# CH32V103C-R0.net
KiCad netlist of a schematic drawn in Altium Designer
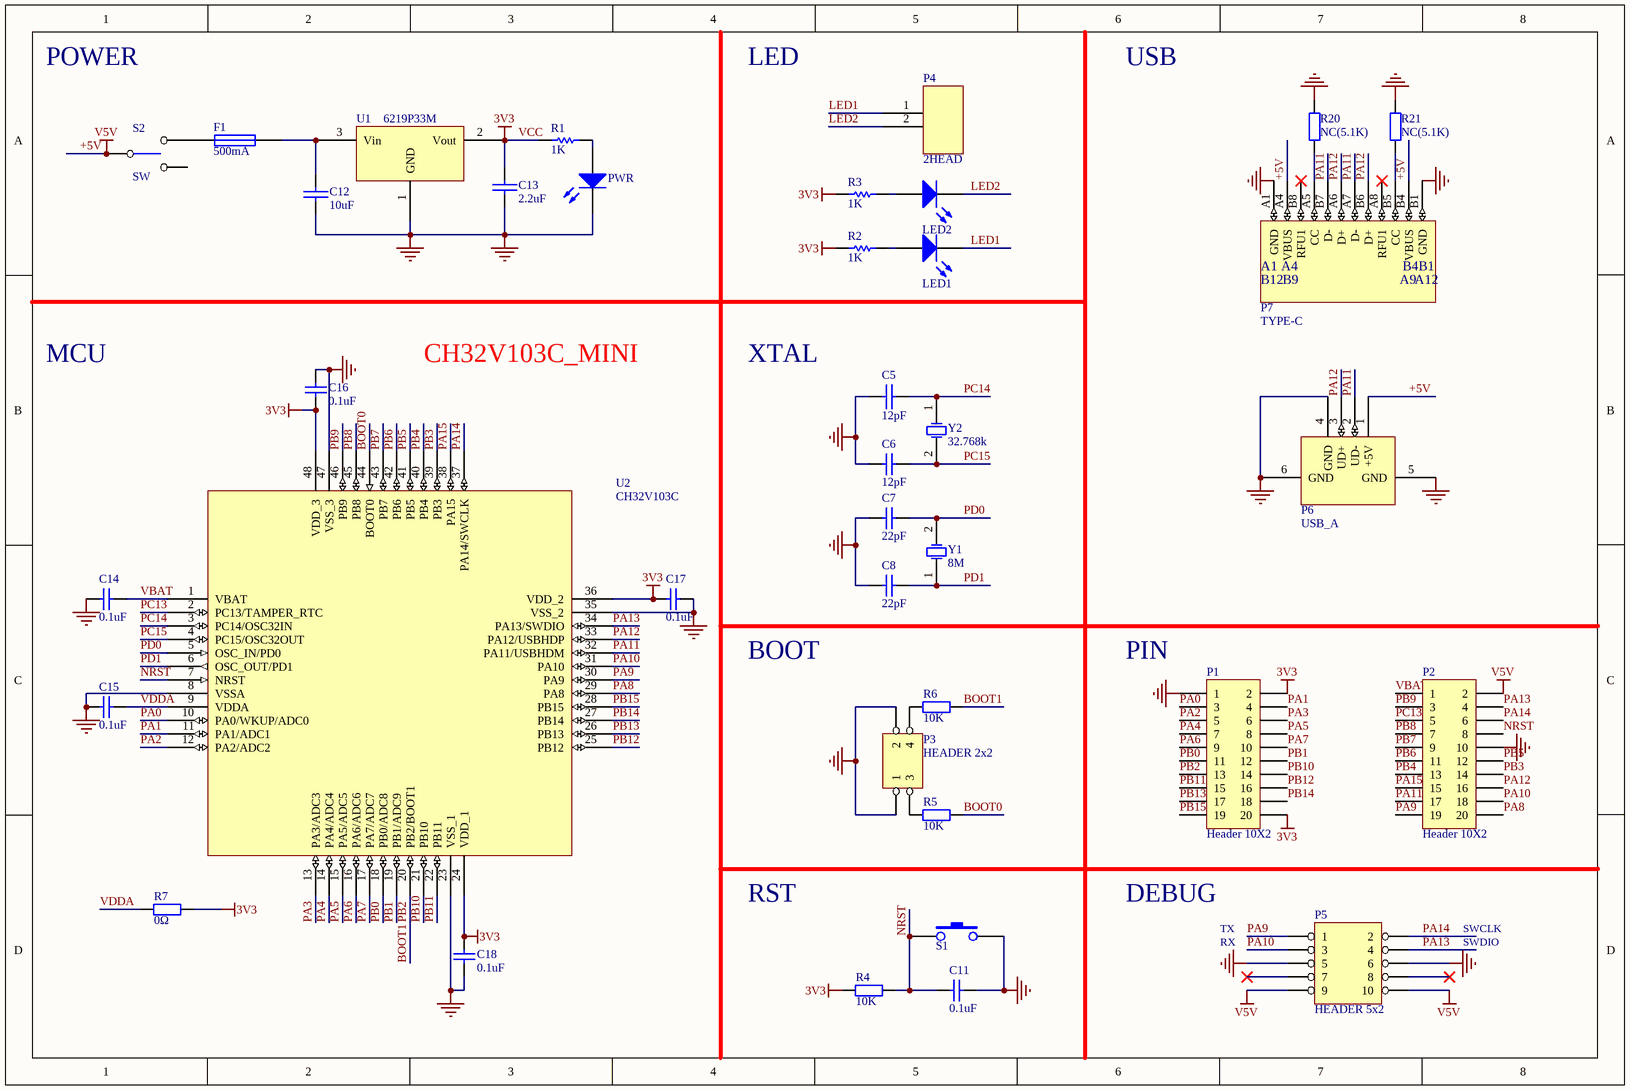
[diagram p0: CH32V103C-R0.SchDoc]

(export (version "E")
  (design (tool "Eeschema 10.0.6"))
  (components
    (comp (ref "C5")
      (value "12pF")
      (footprint "0603_C")
      (description "Capacitor")
      (libsource (lib "wch_sch_others") (part "CAP"))
    )
    (comp (ref "C6")
      (value "12pF")
      (footprint "0603_C")
      (description "Capacitor")
      (fields (field (name "PUBLISHER") "Altium Limited"))
      (libsource (lib "*") (part "Cap"))
    )
    (comp (ref "C7")
      (value "22pF")
      (footprint "0603_C")
      (description "Capacitor")
      (fields (field (name "PUBLISHER") "Altium Limited"))
      (libsource (lib "*") (part "Cap"))
    )
    (comp (ref "C8")
      (value "22pF")
      (footprint "0603_C")
      (description "Capacitor")
      (fields (field (name "PUBLISHER") "Altium Limited"))
      (libsource (lib "*") (part "Cap"))
    )
    (comp (ref "C11")
      (value "0.1uF")
      (footprint "0603_C")
      (description "Capacitor")
      (fields (field (name "PUBLISHER") "Altium Limited"))
      (libsource (lib "*") (part "Cap"))
    )
    (comp (ref "C12")
      (value "10uF")
      (footprint "3216_C")
      (description "Capacitor")
      (libsource (lib "wch_sch_others") (part "CAP"))
    )
    (comp (ref "C13")
      (value "2.2uF")
      (footprint "0603_C")
      (description "Capacitor")
      (libsource (lib "wch_sch_others") (part "CAP"))
    )
    (comp (ref "C14")
      (value "0.1uF")
      (footprint "0603_C")
      (description "Capacitor")
      (fields (field (name "PUBLISHER") "Altium Limited"))
      (libsource (lib "*") (part "Cap"))
    )
    (comp (ref "C15")
      (value "0.1uF")
      (footprint "0603_C")
      (description "Capacitor")
      (fields (field (name "PUBLISHER") "Altium Limited"))
      (libsource (lib "*") (part "Cap"))
    )
    (comp (ref "C16")
      (value "0.1uF")
      (footprint "0603_C")
      (description "Capacitor")
      (fields (field (name "PUBLISHER") "Altium Limited"))
      (libsource (lib "*") (part "Cap"))
    )
    (comp (ref "C17")
      (value "0.1uF")
      (footprint "0603_C")
      (description "Capacitor")
      (fields (field (name "PUBLISHER") "Altium Limited"))
      (libsource (lib "*") (part "Cap"))
    )
    (comp (ref "C18")
      (value "0.1uF")
      (footprint "0603_C")
      (description "Capacitor")
      (fields (field (name "PUBLISHER") "Altium Limited"))
      (libsource (lib "*") (part "Cap"))
    )
    (comp (ref "F1")
      (value "500mA")
      (footprint "0603")
      (description "Fuse")
      (libsource (lib "*") (part "FUSE1"))
    )
    (comp (ref "LED1")
      (value "LED1   blue")
      (footprint "0603+")
      (description "Typical INFRARED GaAs LED")
      (fields (field (name "PUBLISHER") "Altium Limited"))
      (libsource (lib "*") (part "LED0"))
    )
    (comp (ref "LED2")
      (value "LED2  blue")
      (footprint "0603+")
      (description "Typical INFRARED GaAs LED")
      (fields (field (name "PUBLISHER") "Altium Limited"))
      (libsource (lib "*") (part "LED0"))
    )
    (comp (ref "P1")
      (value "Header 10X2")
      (footprint "IDC20-2.54mm")
      (description "Header, 10-Pin, Dual row")
      (fields (field (name "PUBLISHER") "Altium Limited"))
      (libsource (lib "*") (part "Header 10X2"))
    )
    (comp (ref "P2")
      (value "Header 10X2")
      (footprint "IDC20-2.54mm")
      (description "Header, 10-Pin, Dual row")
      (fields (field (name "PUBLISHER") "Altium Limited"))
      (libsource (lib "*") (part "Header 10X2"))
    )
    (comp (ref "P3")
      (value "HEADER 2x2")
      (footprint "MYPCB:IDC4-2.54MM")
      (description "Header, 2-Pin, Dual row")
      (libsource (lib "wch_sch_others") (part "HEADER 2x2"))
    )
    (comp (ref "P4") (value "2HEAD") (footprint "SIP2-2.54mm") (libsource (lib "*") (part "2HEAD")))
    (comp (ref "P5")
      (value "HEADER 5x2")
      (footprint "MYPCB:IDC10-2.54mm")
      (description "Header, 4-Pin, Dual row")
      (libsource (lib "wch_sch_others") (part "HEADER 5x2"))
    )
    (comp (ref "P6")
      (value "USB_A")
      (footprint "USBAF")
      (description "USB Port")
      (libsource (lib "*") (part "USB"))
    )
    (comp (ref "P7")
      (value "TYPE-C")
      (footprint "TYPE-C-Receptacle-2.0")
      (libsource (lib "*") (part "TYPE-C1"))
    )
    (comp (ref "PWR")
      (value "POWER  red")
      (footprint "0603+")
      (description "Typical INFRARED GaAs LED")
      (fields (field (name "PUBLISHER") "Altium Limited"))
      (libsource (lib "*") (part "LED0"))
    )
    (comp (ref "R1")
      (value "1K")
      (footprint "0603")
      (description "Semiconductor Resistor")
      (fields (field (name "PUBLISHER") "Altium Limited"))
      (libsource (lib "*") (part "Res Semi"))
    )
    (comp (ref "R2")
      (value "1K")
      (footprint "0603")
      (description "Semiconductor Resistor")
      (fields (field (name "PUBLISHER") "Altium Limited"))
      (libsource (lib "*") (part "Res Semi"))
    )
    (comp (ref "R3")
      (value "1K")
      (footprint "0603")
      (description "Semiconductor Resistor")
      (fields (field (name "PUBLISHER") "Altium Limited"))
      (libsource (lib "*") (part "Res Semi"))
    )
    (comp (ref "R4")
      (value "10K")
      (footprint "0603")
      (description "Resistor")
      (fields (field (name "PUBLISHER") "Altium Limited"))
      (libsource (lib "*") (part "Res2"))
    )
    (comp (ref "R5")
      (value "10K")
      (footprint "0603")
      (description "Resistor")
      (fields (field (name "PUBLISHER") "Altium Limited"))
      (libsource (lib "*") (part "Res2"))
    )
    (comp (ref "R6")
      (value "10K")
      (footprint "0603")
      (description "Resistor")
      (fields (field (name "PUBLISHER") "Altium Limited"))
      (libsource (lib "*") (part "Res2"))
    )
    (comp (ref "R7")
      (value "0Ω")
      (footprint "0603")
      (description "Resistor")
      (fields (field (name "PUBLISHER") "Altium Limited"))
      (libsource (lib "*") (part "Res2"))
    )
    (comp (ref "R20")
      (value "NC(5.1K)")
      (footprint "0603")
      (description "Resistor")
      (libsource (lib "Miscellaneous Devices") (part "Res2"))
    )
    (comp (ref "R21")
      (value "NC(5.1K)")
      (footprint "0603")
      (description "Resistor")
      (libsource (lib "Miscellaneous Devices") (part "Res2"))
    )
    (comp (ref "S1") (value "KEY") (footprint "贴片按键") (libsource (lib "*") (part "KEY")))
    (comp (ref "S2") (value "SW") (footprint "KEY2") (libsource (lib "*") (part "SW")))
    (comp (ref "U1")
      (value "6219P33M")
      (footprint "SOT-23")
      (libsource (lib "wch_sch_others") (part "6219P33M"))
    )
    (comp (ref "U2")
      (value "CH32V103C")
      (footprint "LQFP48")
      (description "RISC-V MCU with USB device & USB host & ADC & Touch Key")
      (libsource (lib "CHXXX") (part "CH32V103C"))
    )
    (comp (ref "Y1")
      (value "8M")
      (footprint "XT_AT49")
      (description "Crystal Oscillator")
      (fields (field (name "PUBLISHER") "Altium Limited"))
      (libsource (lib "*") (part "XTAL"))
    )
    (comp (ref "Y2")
      (value "32.768k")
      (footprint "FC-135")
      (description "Crystal Oscillator")
      (fields (field (name "PUBLISHER") "Altium Limited"))
      (libsource (lib "*") (part "XTAL"))
    )
  )
  (nets
    (net (code "2") (name "/BOOT0") (class "Default")
      (node (ref "R5") (pin "1") (pinfunction "1_1") (pintype "passive"))
      (node (ref "U2") (pin "44") (pinfunction "BOOT0_44") (pintype "input"))
    )
    (net (code "3") (name "/BOOT1") (class "Default")
      (node (ref "P1") (pin "13") (pinfunction "13_13") (pintype "passive"))
      (node (ref "R6") (pin "1") (pinfunction "1_1") (pintype "passive"))
      (node (ref "U2") (pin "20") (pinfunction "PB2/BOOT1_20") (pintype "bidirectional"))
    )
    (net (code "4") (name "/LED1") (class "Default")
      (node (ref "LED1") (pin "2") (pinfunction "K_2") (pintype "passive"))
      (node (ref "P4") (pin "1") (pintype "passive"))
    )
    (net (code "5") (name "/LED2") (class "Default")
      (node (ref "LED2") (pin "2") (pinfunction "K_2") (pintype "passive"))
      (node (ref "P4") (pin "2") (pintype "passive"))
    )
    (net (code "6") (name "/NRST") (class "Default")
      (node (ref "C11") (pin "2") (pinfunction "2_2") (pintype "passive"))
      (node (ref "P2") (pin "8") (pinfunction "8_8") (pintype "passive"))
      (node (ref "R4") (pin "1") (pinfunction "1_1") (pintype "passive"))
      (node (ref "S1") (pin "1") (pinfunction "1_1") (pintype "passive"))
      (node (ref "U2") (pin "7") (pinfunction "NRST_7") (pintype "input"))
    )
    (net (code "7") (name "/PA0") (class "Default")
      (node (ref "P1") (pin "3") (pinfunction "3_3") (pintype "passive"))
      (node (ref "U2") (pin "10") (pinfunction "PA0/WKUP/ADC0_10") (pintype "bidirectional"))
    )
    (net (code "8") (name "/PA1") (class "Default")
      (node (ref "P1") (pin "4") (pinfunction "4_4") (pintype "passive"))
      (node (ref "U2") (pin "11") (pinfunction "PA1/ADC1_11") (pintype "bidirectional"))
    )
    (net (code "9") (name "/PA2") (class "Default")
      (node (ref "P1") (pin "5") (pinfunction "5_5") (pintype "passive"))
      (node (ref "U2") (pin "12") (pinfunction "PA2/ADC2_12") (pintype "bidirectional"))
    )
    (net (code "10") (name "/PA3") (class "Default")
      (node (ref "P1") (pin "6") (pinfunction "6_6") (pintype "passive"))
      (node (ref "U2") (pin "13") (pinfunction "PA3/ADC3_13") (pintype "bidirectional"))
    )
    (net (code "11") (name "/PA4") (class "Default")
      (node (ref "P1") (pin "7") (pinfunction "7_7") (pintype "passive"))
      (node (ref "U2") (pin "14") (pinfunction "PA4/ADC4_14") (pintype "bidirectional"))
    )
    (net (code "12") (name "/PA5") (class "Default")
      (node (ref "P1") (pin "8") (pinfunction "8_8") (pintype "passive"))
      (node (ref "U2") (pin "15") (pinfunction "PA5/ADC5_15") (pintype "bidirectional"))
    )
    (net (code "13") (name "/PA6") (class "Default")
      (node (ref "P1") (pin "9") (pinfunction "9_9") (pintype "passive"))
      (node (ref "U2") (pin "16") (pinfunction "PA6/ADC6_16") (pintype "bidirectional"))
    )
    (net (code "14") (name "/PA7") (class "Default")
      (node (ref "P1") (pin "10") (pinfunction "10_10") (pintype "passive"))
      (node (ref "U2") (pin "17") (pinfunction "PA7/ADC7_17") (pintype "bidirectional"))
    )
    (net (code "15") (name "/PA8") (class "Default")
      (node (ref "P2") (pin "20") (pinfunction "20_20") (pintype "passive"))
      (node (ref "U2") (pin "29") (pinfunction "PA8_29") (pintype "bidirectional"))
    )
    (net (code "16") (name "/PA9") (class "Default")
      (node (ref "P2") (pin "19") (pinfunction "19_19") (pintype "passive"))
      (node (ref "P5") (pin "1") (pinfunction "1_1") (pintype "passive"))
      (node (ref "U2") (pin "30") (pinfunction "PA9_30") (pintype "bidirectional"))
    )
    (net (code "17") (name "/PA10") (class "Default")
      (node (ref "P2") (pin "18") (pinfunction "18_18") (pintype "passive"))
      (node (ref "P5") (pin "3") (pinfunction "3_3") (pintype "passive"))
      (node (ref "U2") (pin "31") (pinfunction "PA10_31") (pintype "bidirectional"))
    )
    (net (code "18") (name "/PA11") (class "Default")
      (node (ref "P2") (pin "17") (pinfunction "17_17") (pintype "passive"))
      (node (ref "P6") (pin "2") (pinfunction "UD-_2") (pintype "bidirectional"))
      (node (ref "P7") (pin "A7") (pinfunction "D-_A7") (pintype "bidirectional"))
      (node (ref "P7") (pin "B7") (pinfunction "D-_B7") (pintype "bidirectional"))
      (node (ref "U2") (pin "32") (pinfunction "PA11/USBHDM_32") (pintype "bidirectional"))
    )
    (net (code "19") (name "/PA12") (class "Default")
      (node (ref "P2") (pin "16") (pinfunction "16_16") (pintype "passive"))
      (node (ref "P6") (pin "3") (pinfunction "UD+_3") (pintype "bidirectional"))
      (node (ref "P7") (pin "A6") (pinfunction "D+_A6") (pintype "bidirectional"))
      (node (ref "P7") (pin "B6") (pinfunction "D+_B6") (pintype "bidirectional"))
      (node (ref "U2") (pin "33") (pinfunction "PA12/USBHDP_33") (pintype "bidirectional"))
    )
    (net (code "20") (name "/PA13") (class "Default")
      (node (ref "P2") (pin "4") (pinfunction "4_4") (pintype "passive"))
      (node (ref "P5") (pin "4") (pinfunction "4_4") (pintype "passive"))
      (node (ref "U2") (pin "34") (pinfunction "PA13/SWDIO_34") (pintype "bidirectional"))
    )
    (net (code "21") (name "/PA14") (class "Default")
      (node (ref "P2") (pin "6") (pinfunction "6_6") (pintype "passive"))
      (node (ref "P5") (pin "2") (pinfunction "2_2") (pintype "passive"))
      (node (ref "U2") (pin "37") (pinfunction "PA14/SWCLK_37") (pintype "bidirectional"))
    )
    (net (code "22") (name "/PA15") (class "Default")
      (node (ref "P2") (pin "15") (pinfunction "15_15") (pintype "passive"))
      (node (ref "U2") (pin "38") (pinfunction "PA15_38") (pintype "bidirectional"))
    )
    (net (code "23") (name "/PB0") (class "Default")
      (node (ref "P1") (pin "11") (pinfunction "11_11") (pintype "passive"))
      (node (ref "U2") (pin "18") (pinfunction "PB0/ADC8_18") (pintype "bidirectional"))
    )
    (net (code "24") (name "/PB1") (class "Default")
      (node (ref "P1") (pin "12") (pinfunction "12_12") (pintype "passive"))
      (node (ref "U2") (pin "19") (pinfunction "PB1/ADC9_19") (pintype "bidirectional"))
    )
    (net (code "25") (name "/PB3") (class "Default")
      (node (ref "P2") (pin "14") (pinfunction "14_14") (pintype "passive"))
      (node (ref "U2") (pin "39") (pinfunction "PB3_39") (pintype "bidirectional"))
    )
    (net (code "26") (name "/PB4") (class "Default")
      (node (ref "P2") (pin "13") (pinfunction "13_13") (pintype "passive"))
      (node (ref "U2") (pin "40") (pinfunction "PB4_40") (pintype "bidirectional"))
    )
    (net (code "27") (name "/PB5") (class "Default")
      (node (ref "P2") (pin "12") (pinfunction "12_12") (pintype "passive"))
      (node (ref "U2") (pin "41") (pinfunction "PB5_41") (pintype "bidirectional"))
    )
    (net (code "28") (name "/PB6") (class "Default")
      (node (ref "P2") (pin "11") (pinfunction "11_11") (pintype "passive"))
      (node (ref "U2") (pin "42") (pinfunction "PB6_42") (pintype "bidirectional"))
    )
    (net (code "29") (name "/PB7") (class "Default")
      (node (ref "P2") (pin "9") (pinfunction "9_9") (pintype "passive"))
      (node (ref "U2") (pin "43") (pinfunction "PB7_43") (pintype "bidirectional"))
    )
    (net (code "30") (name "/PB8") (class "Default")
      (node (ref "P2") (pin "7") (pinfunction "7_7") (pintype "passive"))
      (node (ref "U2") (pin "45") (pinfunction "PB8_45") (pintype "bidirectional"))
    )
    (net (code "31") (name "/PB9") (class "Default")
      (node (ref "P2") (pin "3") (pinfunction "3_3") (pintype "passive"))
      (node (ref "U2") (pin "46") (pinfunction "PB9_46") (pintype "bidirectional"))
    )
    (net (code "32") (name "/PB10") (class "Default")
      (node (ref "P1") (pin "14") (pinfunction "14_14") (pintype "passive"))
      (node (ref "U2") (pin "21") (pinfunction "PB10_21") (pintype "bidirectional"))
    )
    (net (code "33") (name "/PB11") (class "Default")
      (node (ref "P1") (pin "15") (pinfunction "15_15") (pintype "passive"))
      (node (ref "U2") (pin "22") (pinfunction "PB11_22") (pintype "bidirectional"))
    )
    (net (code "34") (name "/PB12") (class "Default")
      (node (ref "P1") (pin "16") (pinfunction "16_16") (pintype "passive"))
      (node (ref "U2") (pin "25") (pinfunction "PB12_25") (pintype "bidirectional"))
    )
    (net (code "35") (name "/PB13") (class "Default")
      (node (ref "P1") (pin "17") (pinfunction "17_17") (pintype "passive"))
      (node (ref "U2") (pin "26") (pinfunction "PB13_26") (pintype "bidirectional"))
    )
    (net (code "36") (name "/PB14") (class "Default")
      (node (ref "P1") (pin "18") (pinfunction "18_18") (pintype "passive"))
      (node (ref "U2") (pin "27") (pinfunction "PB14_27") (pintype "bidirectional"))
    )
    (net (code "37") (name "/PB15") (class "Default")
      (node (ref "P1") (pin "19") (pinfunction "19_19") (pintype "passive"))
      (node (ref "U2") (pin "28") (pinfunction "PB15_28") (pintype "bidirectional"))
    )
    (net (code "38") (name "/PC13") (class "Default")
      (node (ref "P2") (pin "5") (pinfunction "5_5") (pintype "passive"))
      (node (ref "U2") (pin "2") (pinfunction "PC13/TAMPER_RTC_2") (pintype "bidirectional"))
    )
    (net (code "39") (name "/PC14") (class "Default")
      (node (ref "C5") (pin "2") (pinfunction "2_2") (pintype "passive"))
      (node (ref "U2") (pin "3") (pinfunction "PC14/OSC32IN_3") (pintype "bidirectional"))
      (node (ref "Y2") (pin "1") (pinfunction "OSC1_1") (pintype "passive"))
    )
    (net (code "40") (name "/PC15") (class "Default")
      (node (ref "C6") (pin "1") (pinfunction "1_1") (pintype "passive"))
      (node (ref "U2") (pin "4") (pinfunction "PC15/OSC32OUT_4") (pintype "bidirectional"))
      (node (ref "Y2") (pin "2") (pinfunction "OSC2_2") (pintype "passive"))
    )
    (net (code "41") (name "/PD0") (class "Default")
      (node (ref "C7") (pin "2") (pinfunction "2_2") (pintype "passive"))
      (node (ref "U2") (pin "5") (pinfunction "OSC_IN/PD0_5") (pintype "input"))
      (node (ref "Y1") (pin "2") (pinfunction "OSC2_2") (pintype "passive"))
    )
    (net (code "42") (name "/PD1") (class "Default")
      (node (ref "C8") (pin "2") (pinfunction "2_2") (pintype "passive"))
      (node (ref "U2") (pin "6") (pinfunction "OSC_OUT/PD1_6") (pintype "output"))
      (node (ref "Y1") (pin "1") (pinfunction "OSC1_1") (pintype "passive"))
    )
    (net (code "43") (name "/VBAT") (class "Default")
      (node (ref "C14") (pin "1") (pinfunction "1_1") (pintype "passive"))
      (node (ref "P2") (pin "1") (pinfunction "1_1") (pintype "passive"))
      (node (ref "U2") (pin "1") (pinfunction "VBAT_1") (pintype "power_in"))
    )
    (net (code "44") (name "/VDDA") (class "Default")
      (node (ref "C15") (pin "1") (pinfunction "1_1") (pintype "passive"))
      (node (ref "R7") (pin "2") (pinfunction "2_2") (pintype "passive"))
      (node (ref "U2") (pin "9") (pinfunction "VDDA_9") (pintype "passive"))
    )
    (net (code "45") (name "3V3") (class "Default")
      (node (ref "C13") (pin "2") (pinfunction "2_2") (pintype "passive"))
      (node (ref "C16") (pin "2") (pinfunction "2_2") (pintype "passive"))
      (node (ref "C17") (pin "2") (pinfunction "2_2") (pintype "passive"))
      (node (ref "C18") (pin "2") (pinfunction "2_2") (pintype "passive"))
      (node (ref "P1") (pin "2") (pinfunction "2_2") (pintype "passive"))
      (node (ref "P1") (pin "20") (pinfunction "20_20") (pintype "passive"))
      (node (ref "R1") (pin "2") (pinfunction "2_2") (pintype "passive"))
      (node (ref "R2") (pin "1") (pinfunction "1_1") (pintype "passive"))
      (node (ref "R3") (pin "1") (pinfunction "1_1") (pintype "passive"))
      (node (ref "R4") (pin "2") (pinfunction "2_2") (pintype "passive"))
      (node (ref "R7") (pin "1") (pinfunction "1_1") (pintype "passive"))
      (node (ref "U1") (pin "2") (pinfunction "Vout_2") (pintype "passive"))
      (node (ref "U2") (pin "24") (pinfunction "VDD_1_24") (pintype "passive"))
      (node (ref "U2") (pin "36") (pinfunction "VDD_2_36") (pintype "passive"))
      (node (ref "U2") (pin "48") (pinfunction "VDD_3_48") (pintype "passive"))
    )
    (net (code "46") (name "GND") (class "Default")
      (node (ref "C11") (pin "1") (pinfunction "1_1") (pintype "passive"))
      (node (ref "C12") (pin "2") (pinfunction "2_2") (pintype "passive"))
      (node (ref "C13") (pin "1") (pinfunction "1_1") (pintype "passive"))
      (node (ref "C14") (pin "2") (pinfunction "2_2") (pintype "passive"))
      (node (ref "C15") (pin "2") (pinfunction "2_2") (pintype "passive"))
      (node (ref "C16") (pin "1") (pinfunction "1_1") (pintype "passive"))
      (node (ref "C17") (pin "1") (pinfunction "1_1") (pintype "passive"))
      (node (ref "C18") (pin "1") (pinfunction "1_1") (pintype "passive"))
      (node (ref "C5") (pin "1") (pinfunction "1_1") (pintype "passive"))
      (node (ref "C6") (pin "2") (pinfunction "2_2") (pintype "passive"))
      (node (ref "C7") (pin "1") (pinfunction "1_1") (pintype "passive"))
      (node (ref "C8") (pin "1") (pinfunction "1_1") (pintype "passive"))
      (node (ref "P1") (pin "1") (pinfunction "1_1") (pintype "passive"))
      (node (ref "P2") (pin "10") (pinfunction "10_10") (pintype "passive"))
      (node (ref "P3") (pin "1") (pinfunction "1_1") (pintype "passive"))
      (node (ref "P3") (pin "2") (pinfunction "2_2") (pintype "passive"))
      (node (ref "P5") (pin "5") (pinfunction "5_5") (pintype "passive"))
      (node (ref "P5") (pin "6") (pinfunction "6_6") (pintype "passive"))
      (node (ref "P6") (pin "4") (pinfunction "GND_4") (pintype "power_in"))
      (node (ref "P6") (pin "5") (pinfunction "GND_5") (pintype "power_in"))
      (node (ref "P6") (pin "6") (pinfunction "GND_6") (pintype "power_in"))
      (node (ref "P7") (pin "A1") (pinfunction "GND_A1") (pintype "bidirectional"))
      (node (ref "P7") (pin "B1") (pinfunction "GND_B1") (pintype "bidirectional"))
      (node (ref "PWR") (pin "2") (pinfunction "K_2") (pintype "passive"))
      (node (ref "R20") (pin "2") (pinfunction "2_2") (pintype "passive"))
      (node (ref "R21") (pin "2") (pinfunction "2_2") (pintype "passive"))
      (node (ref "S1") (pin "3") (pinfunction "3_3") (pintype "passive"))
      (node (ref "U1") (pin "1") (pinfunction "GND_1") (pintype "passive"))
      (node (ref "U2") (pin "23") (pinfunction "VSS_1_23") (pintype "passive"))
      (node (ref "U2") (pin "35") (pinfunction "VSS_2_35") (pintype "passive"))
      (node (ref "U2") (pin "47") (pinfunction "VSS_3_47") (pintype "passive"))
      (node (ref "U2") (pin "8") (pinfunction "VSSA_8") (pintype "passive"))
    )
    (net (code "47") (name "Net-(F1-Pad1)") (class "Default")
      (node (ref "F1") (pin "1") (pinfunction "1_1") (pintype "passive"))
      (node (ref "S2") (pin "3") (pinfunction "3_3") (pintype "passive"))
    )
    (net (code "48") (name "Net-(LED1-A)") (class "Default")
      (node (ref "LED1") (pin "1") (pinfunction "A_1") (pintype "passive"))
      (node (ref "R2") (pin "2") (pinfunction "2_2") (pintype "passive"))
    )
    (net (code "49") (name "Net-(LED2-A)") (class "Default")
      (node (ref "LED2") (pin "1") (pinfunction "A_1") (pintype "passive"))
      (node (ref "R3") (pin "2") (pinfunction "2_2") (pintype "passive"))
    )
    (net (code "50") (name "Net-(P3-Pad3)") (class "Default")
      (node (ref "P3") (pin "3") (pinfunction "3_3") (pintype "passive"))
      (node (ref "R5") (pin "2") (pinfunction "2_2") (pintype "passive"))
    )
    (net (code "51") (name "Net-(P3-Pad4)") (class "Default")
      (node (ref "P3") (pin "4") (pinfunction "4_4") (pintype "passive"))
      (node (ref "R6") (pin "2") (pinfunction "2_2") (pintype "passive"))
    )
    (net (code "52") (name "Net-(P7-CC-PadA5)") (class "Default")
      (node (ref "P7") (pin "A5") (pinfunction "CC_A5") (pintype "bidirectional"))
      (node (ref "R20") (pin "1") (pinfunction "1_1") (pintype "passive"))
    )
    (net (code "53") (name "Net-(P7-CC-PadB5)") (class "Default")
      (node (ref "P7") (pin "B5") (pinfunction "CC_B5") (pintype "bidirectional"))
      (node (ref "R21") (pin "1") (pinfunction "1_1") (pintype "passive"))
    )
    (net (code "54") (name "Net-(PWR-A)") (class "Default")
      (node (ref "PWR") (pin "1") (pinfunction "A_1") (pintype "passive"))
      (node (ref "R1") (pin "1") (pinfunction "1_1") (pintype "passive"))
    )
    (net (code "55") (name "Net-(U1-Vin)") (class "Default")
      (node (ref "C12") (pin "1") (pinfunction "1_1") (pintype "passive"))
      (node (ref "F1") (pin "2") (pinfunction "2_2") (pintype "passive"))
      (node (ref "U1") (pin "3") (pinfunction "Vin_3") (pintype "passive"))
    )
    (net (code "56") (name "V5V") (class "Default")
      (node (ref "P2") (pin "2") (pinfunction "2_2") (pintype "passive"))
      (node (ref "P5") (pin "10") (pinfunction "10_10") (pintype "passive"))
      (node (ref "P5") (pin "9") (pinfunction "9_9") (pintype "passive"))
      (node (ref "P6") (pin "1") (pinfunction "+5V_1") (pintype "power_in"))
      (node (ref "P7") (pin "A4") (pinfunction "VBUS_A4") (pintype "bidirectional"))
      (node (ref "P7") (pin "B4") (pinfunction "VBUS_B4") (pintype "bidirectional"))
      (node (ref "S2") (pin "1") (pinfunction "1_1") (pintype "passive"))
    )
    (net (code "57") (name "unconnected-(P5-Pad7)") (class "Default")
      (node (ref "P5") (pin "7") (pinfunction "7_7") (pintype "passive+no_connect"))
    )
    (net (code "58") (name "unconnected-(P5-Pad8)") (class "Default")
      (node (ref "P5") (pin "8") (pinfunction "8_8") (pintype "passive+no_connect"))
    )
    (net (code "59") (name "unconnected-(P7-RFU1-PadA8)") (class "Default")
      (node (ref "P7") (pin "A8") (pinfunction "RFU1_A8") (pintype "bidirectional+no_connect"))
    )
    (net (code "60") (name "unconnected-(P7-RFU1-PadB8)") (class "Default")
      (node (ref "P7") (pin "B8") (pinfunction "RFU1_B8") (pintype "bidirectional+no_connect"))
    )
    (net (code "61") (name "unconnected-(S2-Pad2)") (class "Default")
      (node (ref "S2") (pin "2") (pinfunction "2_2") (pintype "passive"))
    )
  )
)
